# seed-raspi.net
KiCad netlist of a schematic drawn in EAGLE
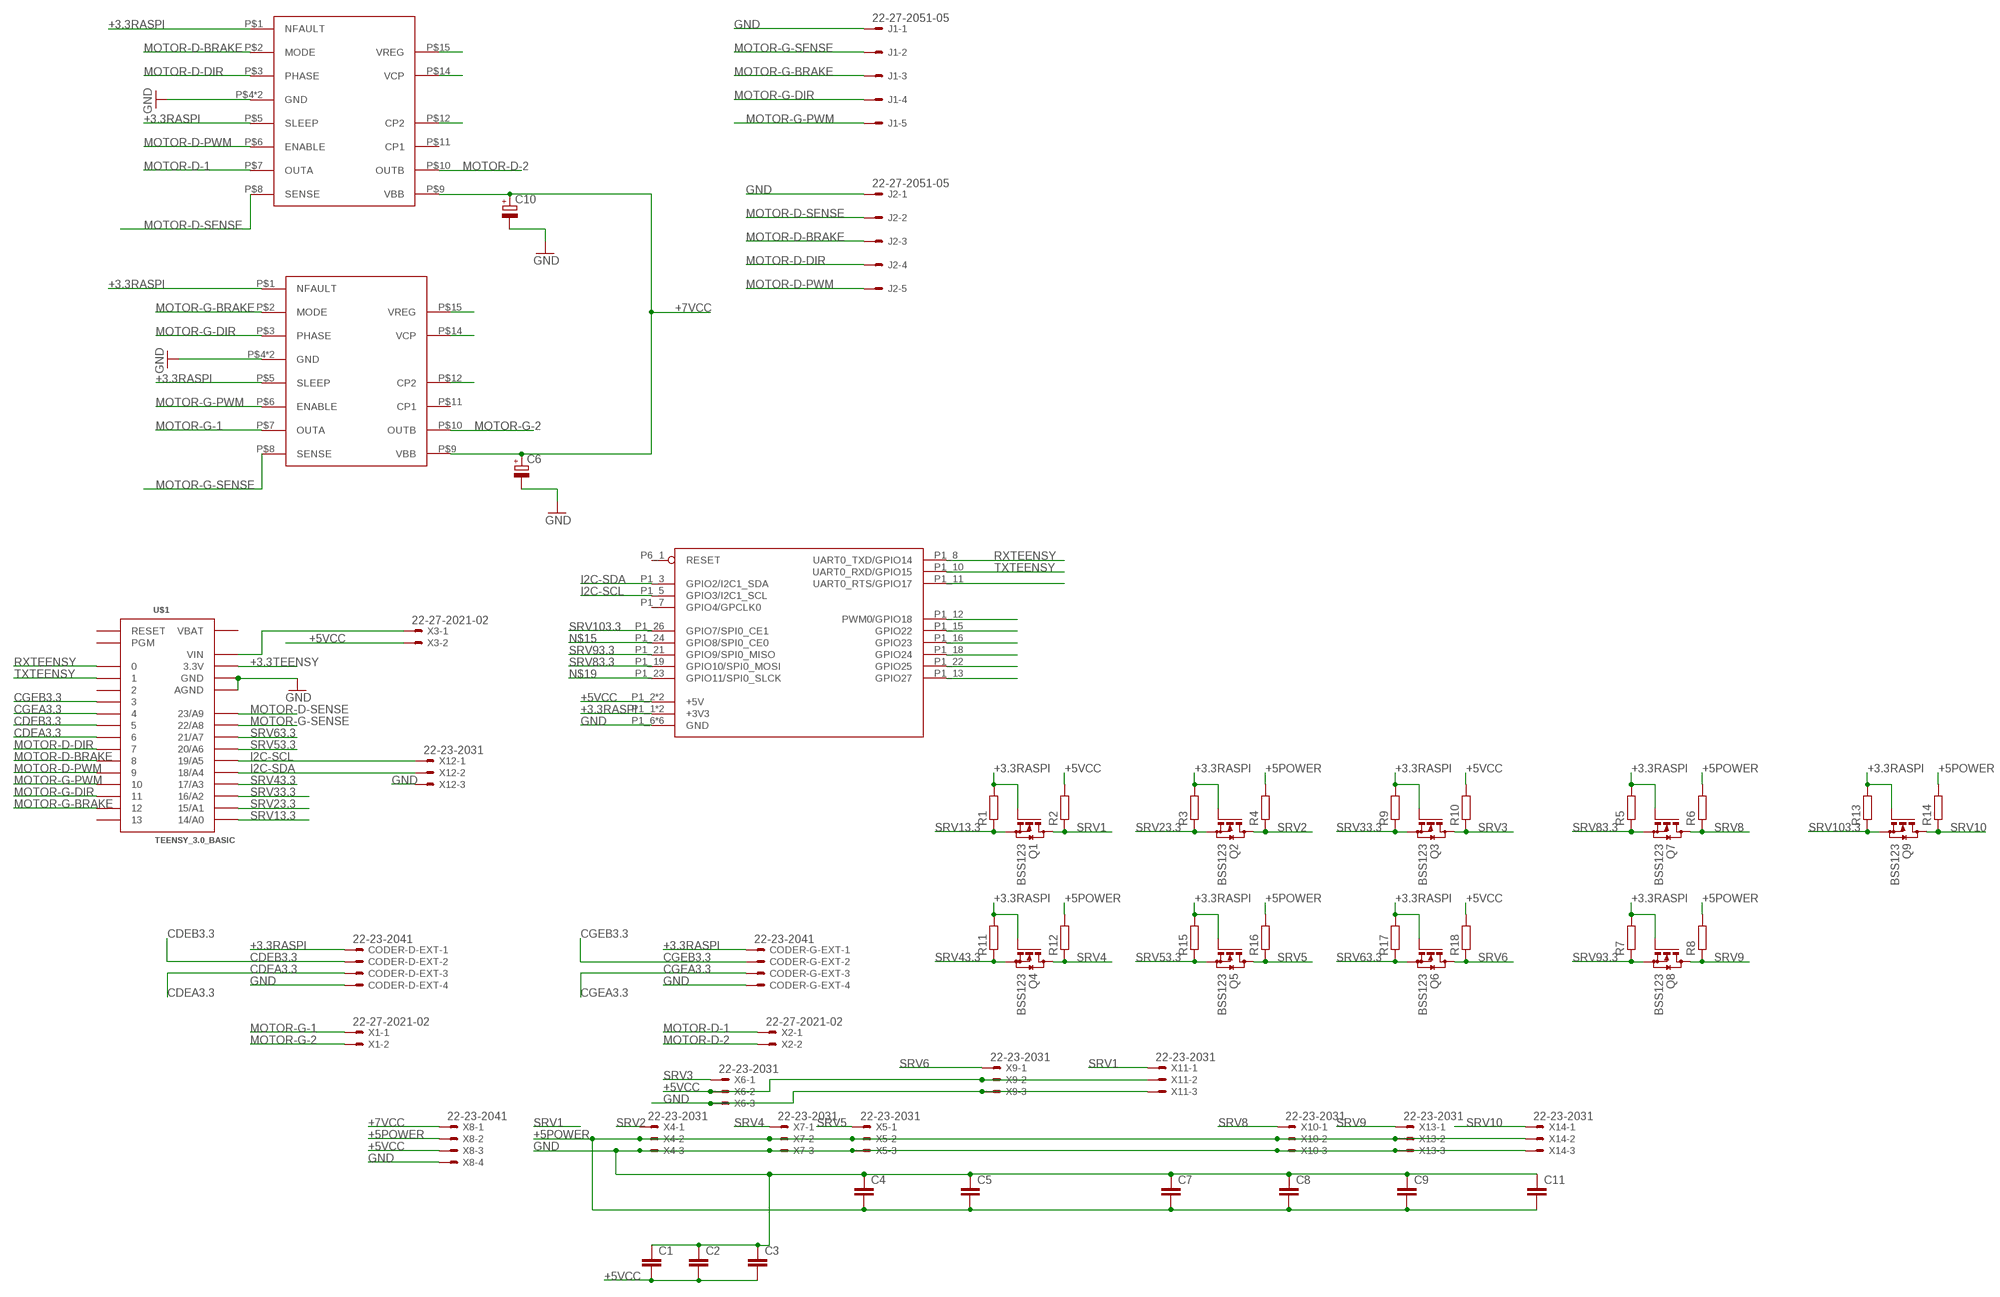
[diagram p0: schematic, sheet 2]
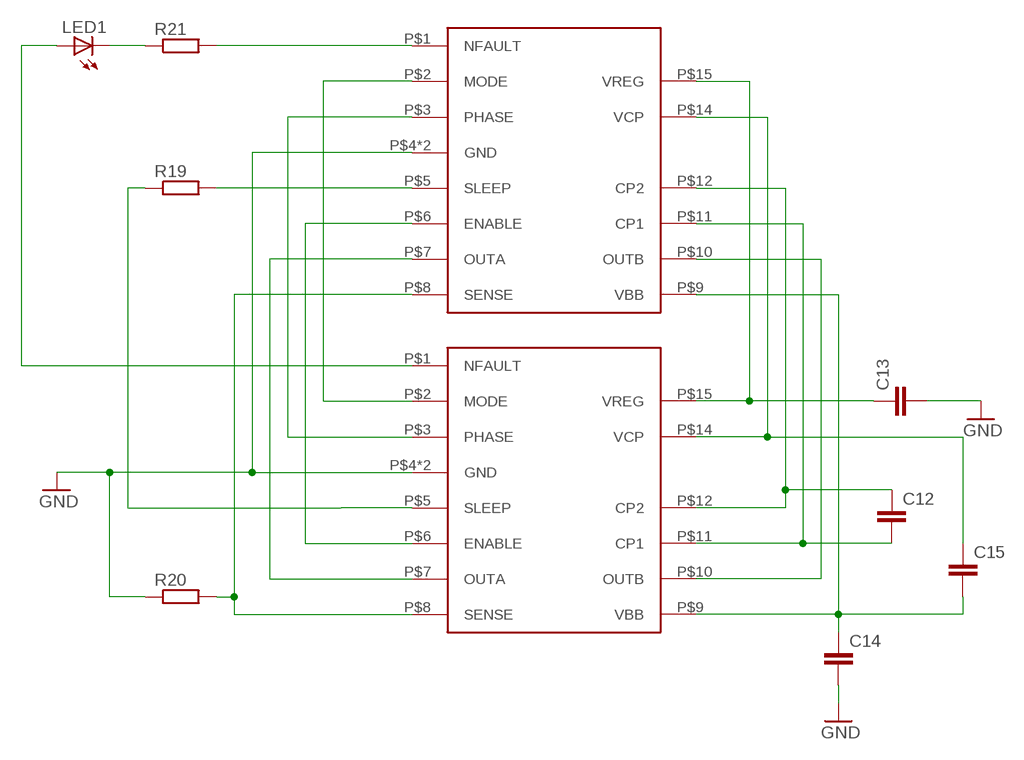
[diagram p1: schematic, sheet 3]
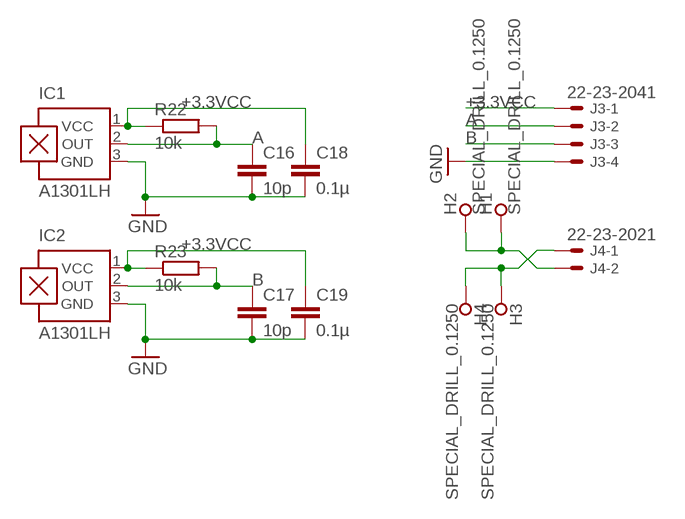
[diagram p2: schematic, sheet 4]
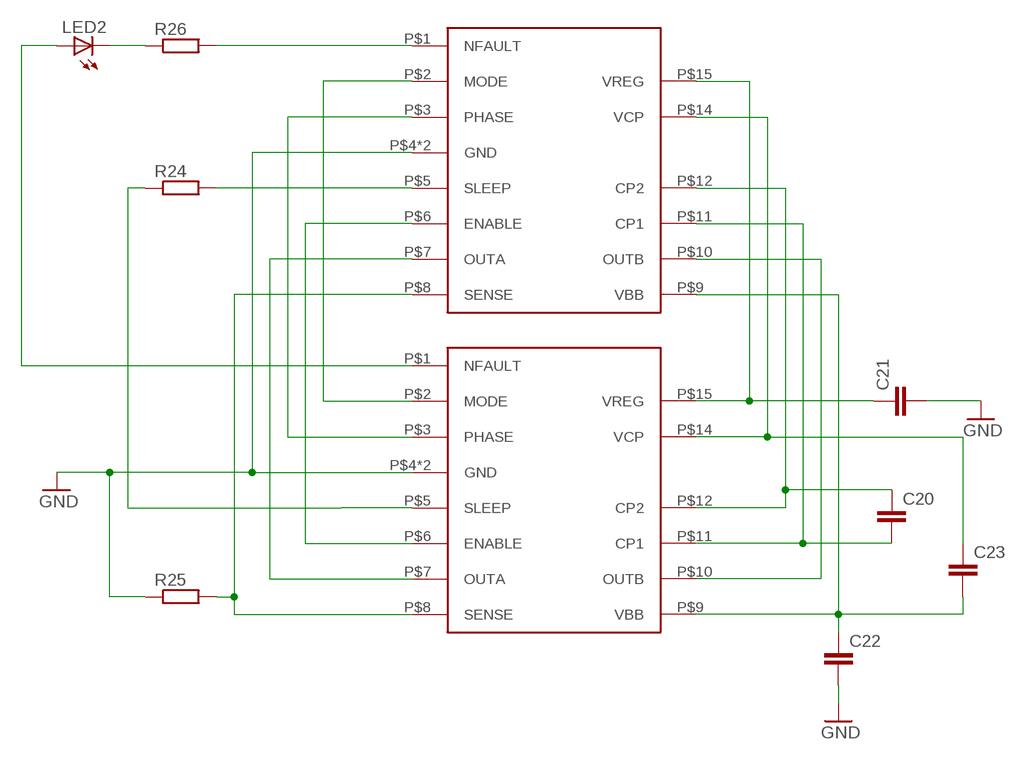
[diagram p3: schematic, sheet 5]
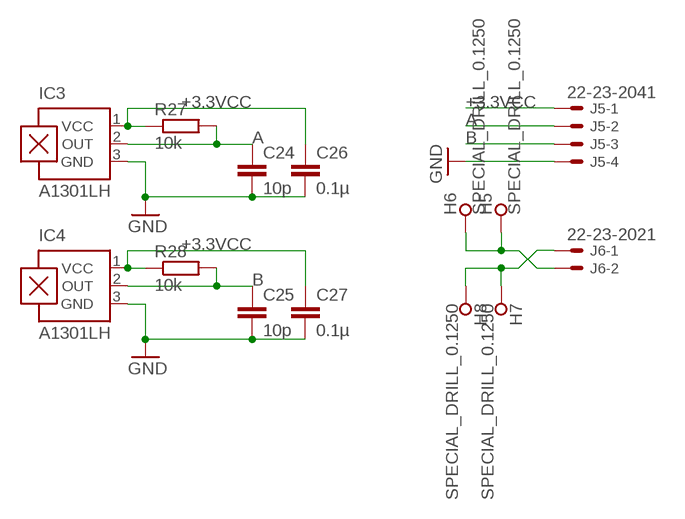
[diagram p4: schematic, sheet 6]
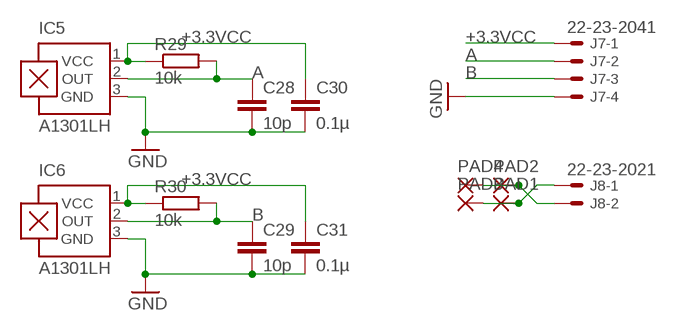
[diagram p5: schematic, sheet 7]

(export (version "E")
  (design (tool "Eeschema 10.0.6"))
  (components
    (comp (ref "C12")
      (value "C-EUC0603")
      (footprint "eagle-import:C0603")
      (libsource (lib "eagle-import") (part "C-EUC0603"))
    )
    (comp (ref "C13")
      (value "C-EUC0603")
      (footprint "eagle-import:C0603")
      (libsource (lib "eagle-import") (part "C-EUC0603"))
    )
    (comp (ref "C14")
      (value "C-EUC0603")
      (footprint "eagle-import:C0603")
      (libsource (lib "eagle-import") (part "C-EUC0603"))
    )
    (comp (ref "C15")
      (value "C-EUC0603")
      (footprint "eagle-import:C0603")
      (libsource (lib "eagle-import") (part "C-EUC0603"))
    )
    (comp (ref "LED1")
      (value "LED3MM")
      (footprint "eagle-import:LED3MM")
      (libsource (lib "eagle-import") (part "LED3MM"))
    )
    (comp (ref "R19")
      (value "R-EU_R0603")
      (footprint "eagle-import:R0603")
      (libsource (lib "eagle-import") (part "R-EU_R0603"))
    )
    (comp (ref "R20")
      (value "R-EU_R0603")
      (footprint "eagle-import:R0603")
      (libsource (lib "eagle-import") (part "R-EU_R0603"))
    )
    (comp (ref "R21")
      (value "R-EU_R0603")
      (footprint "eagle-import:R0603")
      (libsource (lib "eagle-import") (part "R-EU_R0603"))
    )
    (comp (ref "U$5")
      (value "A3950")
      (footprint "eagle-import:16TSSOP")
      (libsource (lib "eagle-import") (part "A3950"))
    )
    (comp (ref "U$6")
      (value "A3950-DIL")
      (footprint "eagle-import:DIL16")
      (libsource (lib "eagle-import") (part "A3950-DIL"))
    )
    (comp (ref "C1")
      (value "C-EUC0603K")
      (footprint "eagle-import:C0603K")
      (libsource (lib "eagle-import") (part "C-EUC0603K"))
    )
    (comp (ref "C2")
      (value "C-EUC0603K")
      (footprint "eagle-import:C0603K")
      (libsource (lib "eagle-import") (part "C-EUC0603K"))
    )
    (comp (ref "C3")
      (value "C-EUC0603K")
      (footprint "eagle-import:C0603K")
      (libsource (lib "eagle-import") (part "C-EUC0603K"))
    )
    (comp (ref "C4")
      (value "C-EUC0603K")
      (footprint "eagle-import:C0603K")
      (libsource (lib "eagle-import") (part "C-EUC0603K"))
    )
    (comp (ref "C5")
      (value "C-EUC0603K")
      (footprint "eagle-import:C0603K")
      (libsource (lib "eagle-import") (part "C-EUC0603K"))
    )
    (comp (ref "C6")
      (value "CPOL-EUE3.5-8")
      (footprint "eagle-import:E3,5-8")
      (libsource (lib "eagle-import") (part "CPOL-EUE3.5-8"))
    )
    (comp (ref "C7")
      (value "C-EUC0603K")
      (footprint "eagle-import:C0603K")
      (libsource (lib "eagle-import") (part "C-EUC0603K"))
    )
    (comp (ref "C8")
      (value "C-EUC0603K")
      (footprint "eagle-import:C0603K")
      (libsource (lib "eagle-import") (part "C-EUC0603K"))
    )
    (comp (ref "C9")
      (value "C-EUC0603K")
      (footprint "eagle-import:C0603K")
      (libsource (lib "eagle-import") (part "C-EUC0603K"))
    )
    (comp (ref "C10")
      (value "CPOL-EUE3.5-8")
      (footprint "eagle-import:E3,5-8")
      (libsource (lib "eagle-import") (part "CPOL-EUE3.5-8"))
    )
    (comp (ref "C11")
      (value "C-EUC0603K")
      (footprint "eagle-import:C0603K")
      (libsource (lib "eagle-import") (part "C-EUC0603K"))
    )
    (comp (ref "CODER-D-EXT")
      (value "22-23-2041")
      (footprint "eagle-import:22-23-2041")
      (fields (field (name "MF") "MOLEX"))
      (libsource (lib "eagle-import") (part "22-23-2041"))
    )
    (comp (ref "CODER-G-EXT")
      (value "22-23-2041")
      (footprint "eagle-import:22-23-2041")
      (fields (field (name "MF") "MOLEX"))
      (libsource (lib "eagle-import") (part "22-23-2041"))
    )
    (comp (ref "J1")
      (value "22-27-2051-05")
      (footprint "eagle-import:6410-05")
      (libsource (lib "eagle-import") (part "22-?-0527-2051"))
    )
    (comp (ref "J2")
      (value "22-27-2051-05")
      (footprint "eagle-import:6410-05")
      (libsource (lib "eagle-import") (part "22-?-0527-2051"))
    )
    (comp (ref "Q1")
      (value "BSS123")
      (footprint "eagle-import:SOT23")
      (libsource (lib "eagle-import") (part "BSS123"))
    )
    (comp (ref "Q2")
      (value "BSS123")
      (footprint "eagle-import:SOT23")
      (libsource (lib "eagle-import") (part "BSS123"))
    )
    (comp (ref "Q3")
      (value "BSS123")
      (footprint "eagle-import:SOT23")
      (libsource (lib "eagle-import") (part "BSS123"))
    )
    (comp (ref "Q4")
      (value "BSS123")
      (footprint "eagle-import:SOT23")
      (libsource (lib "eagle-import") (part "BSS123"))
    )
    (comp (ref "Q5")
      (value "BSS123")
      (footprint "eagle-import:SOT23")
      (libsource (lib "eagle-import") (part "BSS123"))
    )
    (comp (ref "Q6")
      (value "BSS123")
      (footprint "eagle-import:SOT23")
      (libsource (lib "eagle-import") (part "BSS123"))
    )
    (comp (ref "Q7")
      (value "BSS123")
      (footprint "eagle-import:SOT23")
      (libsource (lib "eagle-import") (part "BSS123"))
    )
    (comp (ref "Q8")
      (value "BSS123")
      (footprint "eagle-import:SOT23")
      (libsource (lib "eagle-import") (part "BSS123"))
    )
    (comp (ref "Q9")
      (value "BSS123")
      (footprint "eagle-import:SOT23")
      (libsource (lib "eagle-import") (part "BSS123"))
    )
    (comp (ref "R1")
      (value "R-EU_R0603")
      (footprint "eagle-import:R0603")
      (libsource (lib "eagle-import") (part "R-EU_R0603"))
    )
    (comp (ref "R2")
      (value "R-EU_R0603")
      (footprint "eagle-import:R0603")
      (libsource (lib "eagle-import") (part "R-EU_R0603"))
    )
    (comp (ref "R3")
      (value "R-EU_R0603")
      (footprint "eagle-import:R0603")
      (libsource (lib "eagle-import") (part "R-EU_R0603"))
    )
    (comp (ref "R4")
      (value "R-EU_R0603")
      (footprint "eagle-import:R0603")
      (libsource (lib "eagle-import") (part "R-EU_R0603"))
    )
    (comp (ref "R5")
      (value "R-EU_R0603")
      (footprint "eagle-import:R0603")
      (libsource (lib "eagle-import") (part "R-EU_R0603"))
    )
    (comp (ref "R6")
      (value "R-EU_R0603")
      (footprint "eagle-import:R0603")
      (libsource (lib "eagle-import") (part "R-EU_R0603"))
    )
    (comp (ref "R7")
      (value "R-EU_R0603")
      (footprint "eagle-import:R0603")
      (libsource (lib "eagle-import") (part "R-EU_R0603"))
    )
    (comp (ref "R8")
      (value "R-EU_R0603")
      (footprint "eagle-import:R0603")
      (libsource (lib "eagle-import") (part "R-EU_R0603"))
    )
    (comp (ref "R9")
      (value "R-EU_R0603")
      (footprint "eagle-import:R0603")
      (libsource (lib "eagle-import") (part "R-EU_R0603"))
    )
    (comp (ref "R10")
      (value "R-EU_R0603")
      (footprint "eagle-import:R0603")
      (libsource (lib "eagle-import") (part "R-EU_R0603"))
    )
    (comp (ref "R11")
      (value "R-EU_R0603")
      (footprint "eagle-import:R0603")
      (libsource (lib "eagle-import") (part "R-EU_R0603"))
    )
    (comp (ref "R12")
      (value "R-EU_R0603")
      (footprint "eagle-import:R0603")
      (libsource (lib "eagle-import") (part "R-EU_R0603"))
    )
    (comp (ref "R13")
      (value "R-EU_R0603")
      (footprint "eagle-import:R0603")
      (libsource (lib "eagle-import") (part "R-EU_R0603"))
    )
    (comp (ref "R14")
      (value "R-EU_R0603")
      (footprint "eagle-import:R0603")
      (libsource (lib "eagle-import") (part "R-EU_R0603"))
    )
    (comp (ref "R15")
      (value "R-EU_R0603")
      (footprint "eagle-import:R0603")
      (libsource (lib "eagle-import") (part "R-EU_R0603"))
    )
    (comp (ref "R16")
      (value "R-EU_R0603")
      (footprint "eagle-import:R0603")
      (libsource (lib "eagle-import") (part "R-EU_R0603"))
    )
    (comp (ref "R17")
      (value "R-EU_R0603")
      (footprint "eagle-import:R0603")
      (libsource (lib "eagle-import") (part "R-EU_R0603"))
    )
    (comp (ref "R18")
      (value "R-EU_R0603")
      (footprint "eagle-import:R0603")
      (libsource (lib "eagle-import") (part "R-EU_R0603"))
    )
    (comp (ref "U$1")
      (value "TEENSY_3.0_BASIC")
      (footprint "eagle-import:TEENSY_3.0_BASIC")
      (libsource (lib "eagle-import") (part "TEENSY_3.0_BASIC"))
    )
    (comp (ref "U$2")
      (value "RPI-B-V2SHIELD")
      (footprint "eagle-import:RPI-B-V2-SHIELD")
      (libsource (lib "eagle-import") (part "RPI-B-V2SHIELD"))
    )
    (comp (ref "U$3")
      (value "A3950-DIL")
      (footprint "eagle-import:DIL16")
      (libsource (lib "eagle-import") (part "A3950-DIL"))
    )
    (comp (ref "U$4")
      (value "A3950-DIL")
      (footprint "eagle-import:DIL16")
      (libsource (lib "eagle-import") (part "A3950-DIL"))
    )
    (comp (ref "X1")
      (value "22-27-2021-02")
      (footprint "eagle-import:6410-02")
      (libsource (lib "eagle-import") (part "22-?-0227-2021"))
    )
    (comp (ref "X2")
      (value "22-27-2021-02")
      (footprint "eagle-import:6410-02")
      (libsource (lib "eagle-import") (part "22-?-0227-2021"))
    )
    (comp (ref "X3")
      (value "22-27-2021-02")
      (footprint "eagle-import:6410-02")
      (libsource (lib "eagle-import") (part "22-?-0227-2021"))
    )
    (comp (ref "X4")
      (value "22-23-2031")
      (footprint "eagle-import:22-23-2031")
      (fields (field (name "MF") "MOLEX"))
      (libsource (lib "eagle-import") (part "22-23-2031"))
    )
    (comp (ref "X5")
      (value "22-23-2031")
      (footprint "eagle-import:22-23-2031")
      (fields (field (name "MF") "MOLEX"))
      (libsource (lib "eagle-import") (part "22-23-2031"))
    )
    (comp (ref "X6")
      (value "22-23-2031")
      (footprint "eagle-import:22-23-2031")
      (fields (field (name "MF") "MOLEX"))
      (libsource (lib "eagle-import") (part "22-23-2031"))
    )
    (comp (ref "X7")
      (value "22-23-2031")
      (footprint "eagle-import:22-23-2031")
      (fields (field (name "MF") "MOLEX"))
      (libsource (lib "eagle-import") (part "22-23-2031"))
    )
    (comp (ref "X8")
      (value "22-23-2041")
      (footprint "eagle-import:22-23-2041")
      (fields (field (name "MF") "MOLEX"))
      (libsource (lib "eagle-import") (part "22-23-2041"))
    )
    (comp (ref "X9")
      (value "22-23-2031")
      (footprint "eagle-import:22-23-2031")
      (fields (field (name "MF") "MOLEX"))
      (libsource (lib "eagle-import") (part "22-23-2031"))
    )
    (comp (ref "X10")
      (value "22-23-2031")
      (footprint "eagle-import:22-23-2031")
      (fields (field (name "MF") "MOLEX"))
      (libsource (lib "eagle-import") (part "22-23-2031"))
    )
    (comp (ref "X11")
      (value "22-23-2031")
      (footprint "eagle-import:22-23-2031")
      (fields (field (name "MF") "MOLEX"))
      (libsource (lib "eagle-import") (part "22-23-2031"))
    )
    (comp (ref "X12")
      (value "22-23-2031")
      (footprint "eagle-import:22-23-2031")
      (fields (field (name "MF") "MOLEX"))
      (libsource (lib "eagle-import") (part "22-23-2031"))
    )
    (comp (ref "X13")
      (value "22-23-2031")
      (footprint "eagle-import:22-23-2031")
      (fields (field (name "MF") "MOLEX"))
      (libsource (lib "eagle-import") (part "22-23-2031"))
    )
    (comp (ref "X14")
      (value "22-23-2031")
      (footprint "eagle-import:22-23-2031")
      (fields (field (name "MF") "MOLEX"))
      (libsource (lib "eagle-import") (part "22-23-2031"))
    )
    (comp (ref "C24")
      (value "10p")
      (footprint "eagle-import:C0805")
      (libsource (lib "eagle-import") (part "C-EUC0805"))
    )
    (comp (ref "C25")
      (value "10p")
      (footprint "eagle-import:C0805")
      (libsource (lib "eagle-import") (part "C-EUC0805"))
    )
    (comp (ref "C26")
      (value "0.1µ")
      (footprint "eagle-import:C0805")
      (libsource (lib "eagle-import") (part "C-EUC0805"))
    )
    (comp (ref "C27")
      (value "0.1µ")
      (footprint "eagle-import:C0805")
      (libsource (lib "eagle-import") (part "C-EUC0805"))
    )
    (comp (ref "H5")
      (value "SPECIAL_DRILL_0.1250")
      (footprint "eagle-import:PAD_0.1250")
      (libsource (lib "eagle-import") (part "SPECIAL_DRILL_0.1250"))
    )
    (comp (ref "H6")
      (value "SPECIAL_DRILL_0.1250")
      (footprint "eagle-import:PAD_0.1250")
      (libsource (lib "eagle-import") (part "SPECIAL_DRILL_0.1250"))
    )
    (comp (ref "H7")
      (value "SPECIAL_DRILL_0.1250")
      (footprint "eagle-import:PAD_0.1250")
      (libsource (lib "eagle-import") (part "SPECIAL_DRILL_0.1250"))
    )
    (comp (ref "H8")
      (value "SPECIAL_DRILL_0.1250")
      (footprint "eagle-import:PAD_0.1250")
      (libsource (lib "eagle-import") (part "SPECIAL_DRILL_0.1250"))
    )
    (comp (ref "IC3")
      (value "A1301LH")
      (footprint "eagle-import:SOT23-W")
      (fields (field (name "MF") "ALLEGRO MICROSYSTEMS, INC.") (field (name "MPN") "A1301ELHLT-T"))
      (libsource (lib "eagle-import") (part "A13?LH01"))
    )
    (comp (ref "IC4")
      (value "A1301LH")
      (footprint "eagle-import:SOT23-W")
      (fields (field (name "MF") "ALLEGRO MICROSYSTEMS, INC.") (field (name "MPN") "A1301ELHLT-T"))
      (libsource (lib "eagle-import") (part "A13?LH01"))
    )
    (comp (ref "J5")
      (value "22-23-2041")
      (footprint "eagle-import:22-23-2041")
      (fields (field (name "MF") "MOLEX"))
      (libsource (lib "eagle-import") (part "22-23-2041"))
    )
    (comp (ref "J6")
      (value "22-23-2021")
      (footprint "eagle-import:22-23-2021")
      (fields (field (name "MF") "MOLEX"))
      (libsource (lib "eagle-import") (part "22-23-2021"))
    )
    (comp (ref "R27")
      (value "10k")
      (footprint "eagle-import:R0805")
      (libsource (lib "eagle-import") (part "R-EU_R0805"))
    )
    (comp (ref "R28")
      (value "10k")
      (footprint "eagle-import:R0805")
      (libsource (lib "eagle-import") (part "R-EU_R0805"))
    )
    (comp (ref "C16")
      (value "10p")
      (footprint "eagle-import:C0805")
      (libsource (lib "eagle-import") (part "C-EUC0805"))
    )
    (comp (ref "C17")
      (value "10p")
      (footprint "eagle-import:C0805")
      (libsource (lib "eagle-import") (part "C-EUC0805"))
    )
    (comp (ref "C18")
      (value "0.1µ")
      (footprint "eagle-import:C0805")
      (libsource (lib "eagle-import") (part "C-EUC0805"))
    )
    (comp (ref "C19")
      (value "0.1µ")
      (footprint "eagle-import:C0805")
      (libsource (lib "eagle-import") (part "C-EUC0805"))
    )
    (comp (ref "H1")
      (value "SPECIAL_DRILL_0.1250")
      (footprint "eagle-import:PAD_0.1250")
      (libsource (lib "eagle-import") (part "SPECIAL_DRILL_0.1250"))
    )
    (comp (ref "H2")
      (value "SPECIAL_DRILL_0.1250")
      (footprint "eagle-import:PAD_0.1250")
      (libsource (lib "eagle-import") (part "SPECIAL_DRILL_0.1250"))
    )
    (comp (ref "H3")
      (value "SPECIAL_DRILL_0.1250")
      (footprint "eagle-import:PAD_0.1250")
      (libsource (lib "eagle-import") (part "SPECIAL_DRILL_0.1250"))
    )
    (comp (ref "H4")
      (value "SPECIAL_DRILL_0.1250")
      (footprint "eagle-import:PAD_0.1250")
      (libsource (lib "eagle-import") (part "SPECIAL_DRILL_0.1250"))
    )
    (comp (ref "IC1")
      (value "A1301LH")
      (footprint "eagle-import:SOT23-W")
      (fields (field (name "MF") "ALLEGRO MICROSYSTEMS, INC.") (field (name "MPN") "A1301ELHLT-T"))
      (libsource (lib "eagle-import") (part "A13?LH01"))
    )
    (comp (ref "IC2")
      (value "A1301LH")
      (footprint "eagle-import:SOT23-W")
      (fields (field (name "MF") "ALLEGRO MICROSYSTEMS, INC.") (field (name "MPN") "A1301ELHLT-T"))
      (libsource (lib "eagle-import") (part "A13?LH01"))
    )
    (comp (ref "J3")
      (value "22-23-2041")
      (footprint "eagle-import:22-23-2041")
      (fields (field (name "MF") "MOLEX"))
      (libsource (lib "eagle-import") (part "22-23-2041"))
    )
    (comp (ref "J4")
      (value "22-23-2021")
      (footprint "eagle-import:22-23-2021")
      (fields (field (name "MF") "MOLEX"))
      (libsource (lib "eagle-import") (part "22-23-2021"))
    )
    (comp (ref "R22")
      (value "10k")
      (footprint "eagle-import:R0805")
      (libsource (lib "eagle-import") (part "R-EU_R0805"))
    )
    (comp (ref "R23")
      (value "10k")
      (footprint "eagle-import:R0805")
      (libsource (lib "eagle-import") (part "R-EU_R0805"))
    )
    (comp (ref "C20")
      (value "C-EUC0603")
      (footprint "eagle-import:C0603")
      (libsource (lib "eagle-import") (part "C-EUC0603"))
    )
    (comp (ref "C21")
      (value "C-EUC0603")
      (footprint "eagle-import:C0603")
      (libsource (lib "eagle-import") (part "C-EUC0603"))
    )
    (comp (ref "C22")
      (value "C-EUC0603")
      (footprint "eagle-import:C0603")
      (libsource (lib "eagle-import") (part "C-EUC0603"))
    )
    (comp (ref "C23")
      (value "C-EUC0603")
      (footprint "eagle-import:C0603")
      (libsource (lib "eagle-import") (part "C-EUC0603"))
    )
    (comp (ref "LED2")
      (value "LED3MM")
      (footprint "eagle-import:LED3MM")
      (libsource (lib "eagle-import") (part "LED3MM"))
    )
    (comp (ref "R24")
      (value "R-EU_R0603")
      (footprint "eagle-import:R0603")
      (libsource (lib "eagle-import") (part "R-EU_R0603"))
    )
    (comp (ref "R25")
      (value "R-EU_R0603")
      (footprint "eagle-import:R0603")
      (libsource (lib "eagle-import") (part "R-EU_R0603"))
    )
    (comp (ref "R26")
      (value "R-EU_R0603")
      (footprint "eagle-import:R0603")
      (libsource (lib "eagle-import") (part "R-EU_R0603"))
    )
    (comp (ref "U$7")
      (value "A3950")
      (footprint "eagle-import:16TSSOP")
      (libsource (lib "eagle-import") (part "A3950"))
    )
    (comp (ref "U$8")
      (value "A3950-DIL")
      (footprint "eagle-import:DIL16")
      (libsource (lib "eagle-import") (part "A3950-DIL"))
    )
    (comp (ref "C28")
      (value "10p")
      (footprint "eagle-import:C0805")
      (libsource (lib "eagle-import") (part "C-EUC0805"))
    )
    (comp (ref "C29")
      (value "10p")
      (footprint "eagle-import:C0805")
      (libsource (lib "eagle-import") (part "C-EUC0805"))
    )
    (comp (ref "C30")
      (value "0.1µ")
      (footprint "eagle-import:C0805")
      (libsource (lib "eagle-import") (part "C-EUC0805"))
    )
    (comp (ref "C31")
      (value "0.1µ")
      (footprint "eagle-import:C0805")
      (libsource (lib "eagle-import") (part "C-EUC0805"))
    )
    (comp (ref "IC5")
      (value "A1301LH")
      (footprint "eagle-import:SOT23-W")
      (fields (field (name "MF") "ALLEGRO MICROSYSTEMS, INC.") (field (name "MPN") "A1301ELHLT-T"))
      (libsource (lib "eagle-import") (part "A13?LH01"))
    )
    (comp (ref "IC6")
      (value "A1301LH")
      (footprint "eagle-import:SOT23-W")
      (fields (field (name "MF") "ALLEGRO MICROSYSTEMS, INC.") (field (name "MPN") "A1301ELHLT-T"))
      (libsource (lib "eagle-import") (part "A13?LH01"))
    )
    (comp (ref "J7")
      (value "22-23-2041")
      (footprint "eagle-import:22-23-2041")
      (fields (field (name "MF") "MOLEX"))
      (libsource (lib "eagle-import") (part "22-23-2041"))
    )
    (comp (ref "J8")
      (value "22-23-2021")
      (footprint "eagle-import:22-23-2021")
      (fields (field (name "MF") "MOLEX"))
      (libsource (lib "eagle-import") (part "22-23-2021"))
    )
    (comp (ref "PAD1")
      (value "3,81/1,4")
      (footprint "eagle-import:3,81_1,4")
      (libsource (lib "eagle-import") (part "3,81/1,4"))
    )
    (comp (ref "PAD2")
      (value "3,81/1,4")
      (footprint "eagle-import:3,81_1,4")
      (libsource (lib "eagle-import") (part "3,81/1,4"))
    )
    (comp (ref "PAD3")
      (value "3,81/1,4")
      (footprint "eagle-import:3,81_1,4")
      (libsource (lib "eagle-import") (part "3,81/1,4"))
    )
    (comp (ref "PAD4")
      (value "3,81/1,4")
      (footprint "eagle-import:3,81_1,4")
      (libsource (lib "eagle-import") (part "3,81/1,4"))
    )
    (comp (ref "R29")
      (value "10k")
      (footprint "eagle-import:R0805")
      (libsource (lib "eagle-import") (part "R-EU_R0805"))
    )
    (comp (ref "R30")
      (value "10k")
      (footprint "eagle-import:R0805")
      (libsource (lib "eagle-import") (part "R-EU_R0805"))
    )
  )
  (nets
    (net (code "1") (name "+3.3RASPI") (class "Default")
      (node (ref "CODER-D-EXT") (pin "1") (pinfunction "S_1") (pintype "passive"))
      (node (ref "CODER-G-EXT") (pin "1") (pinfunction "S_1") (pintype "passive"))
      (node (ref "Q1") (pin "1") (pinfunction "G_1") (pintype "passive"))
      (node (ref "Q2") (pin "1") (pinfunction "G_1") (pintype "passive"))
      (node (ref "Q3") (pin "1") (pinfunction "G_1") (pintype "passive"))
      (node (ref "Q4") (pin "1") (pinfunction "G_1") (pintype "passive"))
      (node (ref "Q5") (pin "1") (pinfunction "G_1") (pintype "passive"))
      (node (ref "Q6") (pin "1") (pinfunction "G_1") (pintype "passive"))
      (node (ref "Q7") (pin "1") (pinfunction "G_1") (pintype "passive"))
      (node (ref "Q8") (pin "1") (pinfunction "G_1") (pintype "passive"))
      (node (ref "Q9") (pin "1") (pinfunction "G_1") (pintype "passive"))
      (node (ref "R1") (pin "2") (pinfunction "2_2") (pintype "passive"))
      (node (ref "R11") (pin "2") (pinfunction "2_2") (pintype "passive"))
      (node (ref "R13") (pin "2") (pinfunction "2_2") (pintype "passive"))
      (node (ref "R15") (pin "2") (pinfunction "2_2") (pintype "passive"))
      (node (ref "R17") (pin "2") (pinfunction "2_2") (pintype "passive"))
      (node (ref "R3") (pin "2") (pinfunction "2_2") (pintype "passive"))
      (node (ref "R5") (pin "2") (pinfunction "2_2") (pintype "passive"))
      (node (ref "R7") (pin "2") (pinfunction "2_2") (pintype "passive"))
      (node (ref "R9") (pin "2") (pinfunction "2_2") (pintype "passive"))
      (node (ref "U$2") (pin "P1_1") (pinfunction "+3V3_P1_1") (pintype "power_in"))
      (node (ref "U$2") (pin "P1_17") (pinfunction "+3V3_P1_17") (pintype "power_in"))
      (node (ref "U$3") (pin "P$1") (pinfunction "NFAULT_P$1") (pintype "bidirectional"))
      (node (ref "U$3") (pin "P$5") (pinfunction "SLEEP_P$5") (pintype "bidirectional"))
      (node (ref "U$4") (pin "P$1") (pinfunction "NFAULT_P$1") (pintype "bidirectional"))
      (node (ref "U$4") (pin "P$5") (pinfunction "SLEEP_P$5") (pintype "bidirectional"))
    )
    (net (code "2") (name "+3.3TEENSY") (class "Default")
      (node (ref "U$1") (pin "3.3V") (pinfunction "3.3V_3.3V") (pintype "power_in"))
      (node (ref "U$1") (pin "3.3V1") (pinfunction "3.3V_3.3V1") (pintype "power_in"))
    )
    (net (code "3") (name "+3.3VCC") (class "Default")
      (node (ref "C18") (pin "1") (pinfunction "1_1") (pintype "passive"))
      (node (ref "C19") (pin "1") (pinfunction "1_1") (pintype "passive"))
      (node (ref "C26") (pin "1") (pinfunction "1_1") (pintype "passive"))
      (node (ref "C27") (pin "1") (pinfunction "1_1") (pintype "passive"))
      (node (ref "C30") (pin "1") (pinfunction "1_1") (pintype "passive"))
      (node (ref "C31") (pin "1") (pinfunction "1_1") (pintype "passive"))
      (node (ref "IC1") (pin "1") (pinfunction "VCC_1") (pintype "power_in"))
      (node (ref "IC2") (pin "1") (pinfunction "VCC_1") (pintype "power_in"))
      (node (ref "IC3") (pin "1") (pinfunction "VCC_1") (pintype "power_in"))
      (node (ref "IC4") (pin "1") (pinfunction "VCC_1") (pintype "power_in"))
      (node (ref "IC5") (pin "1") (pinfunction "VCC_1") (pintype "power_in"))
      (node (ref "IC6") (pin "1") (pinfunction "VCC_1") (pintype "power_in"))
      (node (ref "J3") (pin "1") (pinfunction "S_1") (pintype "passive"))
      (node (ref "J5") (pin "1") (pinfunction "S_1") (pintype "passive"))
      (node (ref "J7") (pin "1") (pinfunction "S_1") (pintype "passive"))
      (node (ref "R22") (pin "1") (pinfunction "1_1") (pintype "passive"))
      (node (ref "R23") (pin "1") (pinfunction "1_1") (pintype "passive"))
      (node (ref "R27") (pin "1") (pinfunction "1_1") (pintype "passive"))
      (node (ref "R28") (pin "1") (pinfunction "1_1") (pintype "passive"))
      (node (ref "R29") (pin "1") (pinfunction "1_1") (pintype "passive"))
      (node (ref "R30") (pin "1") (pinfunction "1_1") (pintype "passive"))
    )
    (net (code "4") (name "+5POWER") (class "Default")
      (node (ref "C11") (pin "2") (pinfunction "2_2") (pintype "passive"))
      (node (ref "C4") (pin "2") (pinfunction "2_2") (pintype "passive"))
      (node (ref "C5") (pin "2") (pinfunction "2_2") (pintype "passive"))
      (node (ref "C7") (pin "2") (pinfunction "2_2") (pintype "passive"))
      (node (ref "C8") (pin "2") (pinfunction "2_2") (pintype "passive"))
      (node (ref "C9") (pin "2") (pinfunction "2_2") (pintype "passive"))
      (node (ref "R12") (pin "2") (pinfunction "2_2") (pintype "passive"))
      (node (ref "R14") (pin "2") (pinfunction "2_2") (pintype "passive"))
      (node (ref "R16") (pin "2") (pinfunction "2_2") (pintype "passive"))
      (node (ref "R4") (pin "2") (pinfunction "2_2") (pintype "passive"))
      (node (ref "R6") (pin "2") (pinfunction "2_2") (pintype "passive"))
      (node (ref "R8") (pin "2") (pinfunction "2_2") (pintype "passive"))
      (node (ref "X10") (pin "2") (pinfunction "S_2") (pintype "passive"))
      (node (ref "X13") (pin "2") (pinfunction "S_2") (pintype "passive"))
      (node (ref "X14") (pin "2") (pinfunction "S_2") (pintype "passive"))
      (node (ref "X4") (pin "2") (pinfunction "S_2") (pintype "passive"))
      (node (ref "X5") (pin "2") (pinfunction "S_2") (pintype "passive"))
      (node (ref "X7") (pin "2") (pinfunction "S_2") (pintype "passive"))
      (node (ref "X8") (pin "2") (pinfunction "S_2") (pintype "passive"))
    )
    (net (code "5") (name "+5VCC") (class "Default")
      (node (ref "C1") (pin "2") (pinfunction "2_2") (pintype "passive"))
      (node (ref "C2") (pin "2") (pinfunction "2_2") (pintype "passive"))
      (node (ref "C3") (pin "2") (pinfunction "2_2") (pintype "passive"))
      (node (ref "R10") (pin "2") (pinfunction "2_2") (pintype "passive"))
      (node (ref "R18") (pin "2") (pinfunction "2_2") (pintype "passive"))
      (node (ref "R2") (pin "2") (pinfunction "2_2") (pintype "passive"))
      (node (ref "U$2") (pin "P1_2") (pinfunction "+5V_P1_2") (pintype "power_in"))
      (node (ref "U$2") (pin "P1_4") (pinfunction "+5V_P1_4") (pintype "power_in"))
      (node (ref "X11") (pin "2") (pinfunction "S_2") (pintype "passive"))
      (node (ref "X3") (pin "2") (pinfunction "S_2") (pintype "passive"))
      (node (ref "X6") (pin "2") (pinfunction "S_2") (pintype "passive"))
      (node (ref "X8") (pin "3") (pinfunction "S_3") (pintype "passive"))
      (node (ref "X9") (pin "2") (pinfunction "S_2") (pintype "passive"))
    )
    (net (code "6") (name "+7VCC") (class "Default")
      (node (ref "C10") (pin "+") (pinfunction "+_+") (pintype "passive"))
      (node (ref "C6") (pin "+") (pinfunction "+_+") (pintype "passive"))
      (node (ref "U$3") (pin "P$9") (pinfunction "VBB_P$9") (pintype "bidirectional"))
      (node (ref "U$4") (pin "P$9") (pinfunction "VBB_P$9") (pintype "bidirectional"))
      (node (ref "X8") (pin "1") (pinfunction "S_1") (pintype "passive"))
    )
    (net (code "7") (name "A") (class "Default")
      (node (ref "C16") (pin "1") (pinfunction "1_1") (pintype "passive"))
      (node (ref "C24") (pin "1") (pinfunction "1_1") (pintype "passive"))
      (node (ref "C28") (pin "1") (pinfunction "1_1") (pintype "passive"))
      (node (ref "IC1") (pin "2") (pinfunction "OUT_2") (pintype "output"))
      (node (ref "IC3") (pin "2") (pinfunction "OUT_2") (pintype "output"))
      (node (ref "IC5") (pin "2") (pinfunction "OUT_2") (pintype "output"))
      (node (ref "J3") (pin "2") (pinfunction "S_2") (pintype "passive"))
      (node (ref "J5") (pin "2") (pinfunction "S_2") (pintype "passive"))
      (node (ref "J7") (pin "2") (pinfunction "S_2") (pintype "passive"))
      (node (ref "R22") (pin "2") (pinfunction "2_2") (pintype "passive"))
      (node (ref "R27") (pin "2") (pinfunction "2_2") (pintype "passive"))
      (node (ref "R29") (pin "2") (pinfunction "2_2") (pintype "passive"))
    )
    (net (code "8") (name "B") (class "Default")
      (node (ref "C17") (pin "1") (pinfunction "1_1") (pintype "passive"))
      (node (ref "C25") (pin "1") (pinfunction "1_1") (pintype "passive"))
      (node (ref "C29") (pin "1") (pinfunction "1_1") (pintype "passive"))
      (node (ref "IC2") (pin "2") (pinfunction "OUT_2") (pintype "output"))
      (node (ref "IC4") (pin "2") (pinfunction "OUT_2") (pintype "output"))
      (node (ref "IC6") (pin "2") (pinfunction "OUT_2") (pintype "output"))
      (node (ref "J3") (pin "3") (pinfunction "S_3") (pintype "passive"))
      (node (ref "J5") (pin "3") (pinfunction "S_3") (pintype "passive"))
      (node (ref "J7") (pin "3") (pinfunction "S_3") (pintype "passive"))
      (node (ref "R23") (pin "2") (pinfunction "2_2") (pintype "passive"))
      (node (ref "R28") (pin "2") (pinfunction "2_2") (pintype "passive"))
      (node (ref "R30") (pin "2") (pinfunction "2_2") (pintype "passive"))
    )
    (net (code "9") (name "CDEA3.3") (class "Default")
      (node (ref "CODER-D-EXT") (pin "3") (pinfunction "S_3") (pintype "passive"))
      (node (ref "U$1") (pin "6") (pinfunction "6_6") (pintype "bidirectional"))
    )
    (net (code "10") (name "CDEB3.3") (class "Default")
      (node (ref "CODER-D-EXT") (pin "2") (pinfunction "S_2") (pintype "passive"))
      (node (ref "U$1") (pin "5") (pinfunction "5_5") (pintype "bidirectional"))
    )
    (net (code "11") (name "CGEA3.3") (class "Default")
      (node (ref "CODER-G-EXT") (pin "3") (pinfunction "S_3") (pintype "passive"))
      (node (ref "U$1") (pin "4") (pinfunction "4_4") (pintype "bidirectional"))
    )
    (net (code "12") (name "CGEB3.3") (class "Default")
      (node (ref "CODER-G-EXT") (pin "2") (pinfunction "S_2") (pintype "passive"))
      (node (ref "U$1") (pin "3") (pinfunction "3_3") (pintype "bidirectional"))
    )
    (net (code "13") (name "GND") (class "Default")
      (node (ref "C1") (pin "1") (pinfunction "1_1") (pintype "passive"))
      (node (ref "C10") (pin "-") (pinfunction "-_-") (pintype "passive"))
      (node (ref "C11") (pin "1") (pinfunction "1_1") (pintype "passive"))
      (node (ref "C13") (pin "2") (pinfunction "2_2") (pintype "passive"))
      (node (ref "C14") (pin "2") (pinfunction "2_2") (pintype "passive"))
      (node (ref "C16") (pin "2") (pinfunction "2_2") (pintype "passive"))
      (node (ref "C17") (pin "2") (pinfunction "2_2") (pintype "passive"))
      (node (ref "C18") (pin "2") (pinfunction "2_2") (pintype "passive"))
      (node (ref "C19") (pin "2") (pinfunction "2_2") (pintype "passive"))
      (node (ref "C2") (pin "1") (pinfunction "1_1") (pintype "passive"))
      (node (ref "C21") (pin "2") (pinfunction "2_2") (pintype "passive"))
      (node (ref "C22") (pin "2") (pinfunction "2_2") (pintype "passive"))
      (node (ref "C24") (pin "2") (pinfunction "2_2") (pintype "passive"))
      (node (ref "C25") (pin "2") (pinfunction "2_2") (pintype "passive"))
      (node (ref "C26") (pin "2") (pinfunction "2_2") (pintype "passive"))
      (node (ref "C27") (pin "2") (pinfunction "2_2") (pintype "passive"))
      (node (ref "C28") (pin "2") (pinfunction "2_2") (pintype "passive"))
      (node (ref "C29") (pin "2") (pinfunction "2_2") (pintype "passive"))
      (node (ref "C3") (pin "1") (pinfunction "1_1") (pintype "passive"))
      (node (ref "C30") (pin "2") (pinfunction "2_2") (pintype "passive"))
      (node (ref "C31") (pin "2") (pinfunction "2_2") (pintype "passive"))
      (node (ref "C4") (pin "1") (pinfunction "1_1") (pintype "passive"))
      (node (ref "C5") (pin "1") (pinfunction "1_1") (pintype "passive"))
      (node (ref "C6") (pin "-") (pinfunction "-_-") (pintype "passive"))
      (node (ref "C7") (pin "1") (pinfunction "1_1") (pintype "passive"))
      (node (ref "C8") (pin "1") (pinfunction "1_1") (pintype "passive"))
      (node (ref "C9") (pin "1") (pinfunction "1_1") (pintype "passive"))
      (node (ref "CODER-D-EXT") (pin "4") (pinfunction "S_4") (pintype "passive"))
      (node (ref "CODER-G-EXT") (pin "4") (pinfunction "S_4") (pintype "passive"))
      (node (ref "IC1") (pin "3") (pinfunction "GND_3") (pintype "power_in"))
      (node (ref "IC2") (pin "3") (pinfunction "GND_3") (pintype "power_in"))
      (node (ref "IC3") (pin "3") (pinfunction "GND_3") (pintype "power_in"))
      (node (ref "IC4") (pin "3") (pinfunction "GND_3") (pintype "power_in"))
      (node (ref "IC5") (pin "3") (pinfunction "GND_3") (pintype "power_in"))
      (node (ref "IC6") (pin "3") (pinfunction "GND_3") (pintype "power_in"))
      (node (ref "J1") (pin "1") (pinfunction "S_1") (pintype "passive"))
      (node (ref "J2") (pin "1") (pinfunction "S_1") (pintype "passive"))
      (node (ref "J3") (pin "4") (pinfunction "S_4") (pintype "passive"))
      (node (ref "J5") (pin "4") (pinfunction "S_4") (pintype "passive"))
      (node (ref "J7") (pin "4") (pinfunction "S_4") (pintype "passive"))
      (node (ref "R20") (pin "1") (pinfunction "1_1") (pintype "passive"))
      (node (ref "R25") (pin "1") (pinfunction "1_1") (pintype "passive"))
      (node (ref "U$1") (pin "AGND") (pinfunction "AGND_AGND") (pintype "power_in"))
      (node (ref "U$1") (pin "GND") (pinfunction "GND_GND") (pintype "power_in"))
      (node (ref "U$1") (pin "GND1") (pinfunction "GND_GND1") (pintype "power_in"))
      (node (ref "U$2") (pin "P1_14") (pinfunction "GND_P1_14") (pintype "power_in"))
      (node (ref "U$2") (pin "P1_20") (pinfunction "GND_P1_20") (pintype "power_in"))
      (node (ref "U$2") (pin "P1_25") (pinfunction "GND_P1_25") (pintype "power_in"))
      (node (ref "U$2") (pin "P1_6") (pinfunction "GND_P1_6") (pintype "power_in"))
      (node (ref "U$2") (pin "P1_9") (pinfunction "GND_P1_9") (pintype "power_in"))
      (node (ref "U$2") (pin "P6_2") (pinfunction "GND_P6_2") (pintype "power_in"))
      (node (ref "U$3") (pin "P$13") (pinfunction "GND_P$13") (pintype "bidirectional"))
      (node (ref "U$3") (pin "P$4") (pinfunction "GND_P$4") (pintype "bidirectional"))
      (node (ref "U$4") (pin "P$13") (pinfunction "GND_P$13") (pintype "bidirectional"))
      (node (ref "U$4") (pin "P$4") (pinfunction "GND_P$4") (pintype "bidirectional"))
      (node (ref "U$5") (pin "P$13") (pinfunction "GND_P$13") (pintype "bidirectional"))
      (node (ref "U$5") (pin "P$4") (pinfunction "GND_P$4") (pintype "bidirectional"))
      (node (ref "U$6") (pin "P$13") (pinfunction "GND_P$13") (pintype "bidirectional"))
      (node (ref "U$6") (pin "P$4") (pinfunction "GND_P$4") (pintype "bidirectional"))
      (node (ref "U$7") (pin "P$13") (pinfunction "GND_P$13") (pintype "bidirectional"))
      (node (ref "U$7") (pin "P$4") (pinfunction "GND_P$4") (pintype "bidirectional"))
      (node (ref "U$8") (pin "P$13") (pinfunction "GND_P$13") (pintype "bidirectional"))
      (node (ref "U$8") (pin "P$4") (pinfunction "GND_P$4") (pintype "bidirectional"))
      (node (ref "X10") (pin "3") (pinfunction "S_3") (pintype "passive"))
      (node (ref "X11") (pin "3") (pinfunction "S_3") (pintype "passive"))
      (node (ref "X12") (pin "3") (pinfunction "S_3") (pintype "passive"))
      (node (ref "X13") (pin "3") (pinfunction "S_3") (pintype "passive"))
      (node (ref "X14") (pin "3") (pinfunction "S_3") (pintype "passive"))
      (node (ref "X4") (pin "3") (pinfunction "S_3") (pintype "passive"))
      (node (ref "X5") (pin "3") (pinfunction "S_3") (pintype "passive"))
      (node (ref "X6") (pin "3") (pinfunction "S_3") (pintype "passive"))
      (node (ref "X7") (pin "3") (pinfunction "S_3") (pintype "passive"))
      (node (ref "X8") (pin "4") (pinfunction "S_4") (pintype "passive"))
      (node (ref "X9") (pin "3") (pinfunction "S_3") (pintype "passive"))
    )
    (net (code "14") (name "I2C-SCL") (class "Default")
      (node (ref "U$1") (pin "19/A5") (pinfunction "19/A5_19/A5") (pintype "bidirectional"))
      (node (ref "U$2") (pin "P1_5") (pinfunction "GPIO3/I2C1_SCL_P1_5") (pintype "bidirectional"))
      (node (ref "X12") (pin "1") (pinfunction "S_1") (pintype "passive"))
    )
    (net (code "15") (name "I2C-SDA") (class "Default")
      (node (ref "U$1") (pin "18/A4") (pinfunction "18/A4_18/A4") (pintype "bidirectional"))
      (node (ref "U$2") (pin "P1_3") (pinfunction "GPIO2/I2C1_SDA_P1_3") (pintype "bidirectional"))
      (node (ref "X12") (pin "2") (pinfunction "S_2") (pintype "passive"))
    )
    (net (code "16") (name "MOTOR-D-1") (class "Default")
      (node (ref "U$4") (pin "P$7") (pinfunction "OUTA_P$7") (pintype "bidirectional"))
      (node (ref "X2") (pin "1") (pinfunction "S_1") (pintype "passive"))
    )
    (net (code "17") (name "MOTOR-D-2") (class "Default")
      (node (ref "U$4") (pin "P$10") (pinfunction "OUTB_P$10") (pintype "bidirectional"))
      (node (ref "X2") (pin "2") (pinfunction "S_2") (pintype "passive"))
    )
    (net (code "18") (name "MOTOR-D-BRAKE") (class "Default")
      (node (ref "J2") (pin "3") (pinfunction "S_3") (pintype "passive"))
      (node (ref "U$1") (pin "8") (pinfunction "8_8") (pintype "bidirectional"))
      (node (ref "U$4") (pin "P$2") (pinfunction "MODE_P$2") (pintype "bidirectional"))
    )
    (net (code "19") (name "MOTOR-D-DIR") (class "Default")
      (node (ref "J2") (pin "4") (pinfunction "S_4") (pintype "passive"))
      (node (ref "U$1") (pin "7") (pinfunction "7_7") (pintype "bidirectional"))
      (node (ref "U$4") (pin "P$3") (pinfunction "PHASE_P$3") (pintype "bidirectional"))
    )
    (net (code "20") (name "MOTOR-D-PWM") (class "Default")
      (node (ref "J2") (pin "5") (pinfunction "S_5") (pintype "passive"))
      (node (ref "U$1") (pin "9") (pinfunction "9_9") (pintype "bidirectional"))
      (node (ref "U$4") (pin "P$6") (pinfunction "ENABLE_P$6") (pintype "bidirectional"))
    )
    (net (code "21") (name "MOTOR-D-SENSE") (class "Default")
      (node (ref "J2") (pin "2") (pinfunction "S_2") (pintype "passive"))
      (node (ref "U$1") (pin "23/A9") (pinfunction "23/A9_23/A9") (pintype "bidirectional"))
      (node (ref "U$4") (pin "P$8") (pinfunction "SENSE_P$8") (pintype "bidirectional"))
    )
    (net (code "22") (name "MOTOR-G-1") (class "Default")
      (node (ref "U$3") (pin "P$7") (pinfunction "OUTA_P$7") (pintype "bidirectional"))
      (node (ref "X1") (pin "1") (pinfunction "S_1") (pintype "passive"))
    )
    (net (code "23") (name "MOTOR-G-2") (class "Default")
      (node (ref "U$3") (pin "P$10") (pinfunction "OUTB_P$10") (pintype "bidirectional"))
      (node (ref "X1") (pin "2") (pinfunction "S_2") (pintype "passive"))
    )
    (net (code "24") (name "MOTOR-G-BRAKE") (class "Default")
      (node (ref "J1") (pin "3") (pinfunction "S_3") (pintype "passive"))
      (node (ref "U$1") (pin "12") (pinfunction "12_12") (pintype "bidirectional"))
      (node (ref "U$3") (pin "P$2") (pinfunction "MODE_P$2") (pintype "bidirectional"))
    )
    (net (code "25") (name "MOTOR-G-DIR") (class "Default")
      (node (ref "J1") (pin "4") (pinfunction "S_4") (pintype "passive"))
      (node (ref "U$1") (pin "11") (pinfunction "11_11") (pintype "bidirectional"))
      (node (ref "U$3") (pin "P$3") (pinfunction "PHASE_P$3") (pintype "bidirectional"))
    )
    (net (code "26") (name "MOTOR-G-PWM") (class "Default")
      (node (ref "J1") (pin "5") (pinfunction "S_5") (pintype "passive"))
      (node (ref "U$1") (pin "10") (pinfunction "10_10") (pintype "bidirectional"))
      (node (ref "U$3") (pin "P$6") (pinfunction "ENABLE_P$6") (pintype "bidirectional"))
    )
    (net (code "27") (name "MOTOR-G-SENSE") (class "Default")
      (node (ref "J1") (pin "2") (pinfunction "S_2") (pintype "passive"))
      (node (ref "U$1") (pin "22/A8") (pinfunction "22/A8_22/A8") (pintype "bidirectional"))
      (node (ref "U$3") (pin "P$8") (pinfunction "SENSE_P$8") (pintype "bidirectional"))
    )
    (net (code "28") (name "N$15") (class "Default")
      (node (ref "U$2") (pin "P1_24") (pinfunction "GPIO8/SPI0_CE0_P1_24") (pintype "bidirectional"))
    )
    (net (code "29") (name "N$19") (class "Default")
      (node (ref "U$2") (pin "P1_23") (pinfunction "GPIO11/SPI0_SLCK_P1_23") (pintype "bidirectional"))
    )
    (net (code "30") (name "Net-(J4A-S)") (class "Default")
      (node (ref "H3") (pin "1") (pinfunction "1_1") (pintype "passive"))
      (node (ref "H4") (pin "1") (pinfunction "1_1") (pintype "passive"))
      (node (ref "J4") (pin "1") (pinfunction "S_1") (pintype "passive"))
    )
    (net (code "31") (name "Net-(J4B-S)") (class "Default")
      (node (ref "H1") (pin "1") (pinfunction "1_1") (pintype "passive"))
      (node (ref "H2") (pin "1") (pinfunction "1_1") (pintype "passive"))
      (node (ref "J4") (pin "2") (pinfunction "S_2") (pintype "passive"))
    )
    (net (code "32") (name "Net-(J6A-S)") (class "Default")
      (node (ref "H7") (pin "1") (pinfunction "1_1") (pintype "passive"))
      (node (ref "H8") (pin "1") (pinfunction "1_1") (pintype "passive"))
      (node (ref "J6") (pin "1") (pinfunction "S_1") (pintype "passive"))
    )
    (net (code "33") (name "Net-(J6B-S)") (class "Default")
      (node (ref "H5") (pin "1") (pinfunction "1_1") (pintype "passive"))
      (node (ref "H6") (pin "1") (pinfunction "1_1") (pintype "passive"))
      (node (ref "J6") (pin "2") (pinfunction "S_2") (pintype "passive"))
    )
    (net (code "34") (name "Net-(J8A-S)") (class "Default")
      (node (ref "J8") (pin "1") (pinfunction "S_1") (pintype "passive"))
      (node (ref "PAD1") (pin "1") (pinfunction "P_1") (pintype "passive"))
      (node (ref "PAD3") (pin "1") (pinfunction "P_1") (pintype "passive"))
    )
    (net (code "35") (name "Net-(J8B-S)") (class "Default")
      (node (ref "J8") (pin "2") (pinfunction "S_2") (pintype "passive"))
      (node (ref "PAD2") (pin "1") (pinfunction "P_1") (pintype "passive"))
      (node (ref "PAD4") (pin "1") (pinfunction "P_1") (pintype "passive"))
    )
    (net (code "36") (name "Net-(LED1-C)") (class "Default")
      (node (ref "LED1") (pin "K") (pinfunction "C_K") (pintype "passive"))
      (node (ref "R21") (pin "1") (pinfunction "1_1") (pintype "passive"))
    )
    (net (code "37") (name "Net-(LED2-C)") (class "Default")
      (node (ref "LED2") (pin "K") (pinfunction "C_K") (pintype "passive"))
      (node (ref "R26") (pin "1") (pinfunction "1_1") (pintype "passive"))
    )
    (net (code "38") (name "Net-(U$5-CP1)") (class "Default")
      (node (ref "C12") (pin "2") (pinfunction "2_2") (pintype "passive"))
      (node (ref "U$5") (pin "P$11") (pinfunction "CP1_P$11") (pintype "bidirectional"))
      (node (ref "U$6") (pin "P$11") (pinfunction "CP1_P$11") (pintype "bidirectional"))
    )
    (net (code "39") (name "Net-(U$5-CP2)") (class "Default")
      (node (ref "C12") (pin "1") (pinfunction "1_1") (pintype "passive"))
      (node (ref "U$5") (pin "P$12") (pinfunction "CP2_P$12") (pintype "bidirectional"))
      (node (ref "U$6") (pin "P$12") (pinfunction "CP2_P$12") (pintype "bidirectional"))
    )
    (net (code "40") (name "Net-(U$5-ENABLE)") (class "Default")
      (node (ref "U$5") (pin "P$6") (pinfunction "ENABLE_P$6") (pintype "bidirectional"))
      (node (ref "U$6") (pin "P$6") (pinfunction "ENABLE_P$6") (pintype "bidirectional"))
    )
    (net (code "41") (name "Net-(U$5-MODE)") (class "Default")
      (node (ref "U$5") (pin "P$2") (pinfunction "MODE_P$2") (pintype "bidirectional"))
      (node (ref "U$6") (pin "P$2") (pinfunction "MODE_P$2") (pintype "bidirectional"))
    )
    (net (code "42") (name "Net-(U$5-NFAULT)") (class "Default")
      (node (ref "R21") (pin "2") (pinfunction "2_2") (pintype "passive"))
      (node (ref "U$5") (pin "P$1") (pinfunction "NFAULT_P$1") (pintype "bidirectional"))
    )
    (net (code "43") (name "Net-(U$5-OUTA)") (class "Default")
      (node (ref "U$5") (pin "P$7") (pinfunction "OUTA_P$7") (pintype "bidirectional"))
      (node (ref "U$6") (pin "P$7") (pinfunction "OUTA_P$7") (pintype "bidirectional"))
    )
    (net (code "44") (name "Net-(U$5-OUTB)") (class "Default")
      (node (ref "U$5") (pin "P$10") (pinfunction "OUTB_P$10") (pintype "bidirectional"))
      (node (ref "U$6") (pin "P$10") (pinfunction "OUTB_P$10") (pintype "bidirectional"))
    )
    (net (code "45") (name "Net-(U$5-PHASE)") (class "Default")
      (node (ref "U$5") (pin "P$3") (pinfunction "PHASE_P$3") (pintype "bidirectional"))
      (node (ref "U$6") (pin "P$3") (pinfunction "PHASE_P$3") (pintype "bidirectional"))
    )
    (net (code "46") (name "Net-(U$5-SENSE)") (class "Default")
      (node (ref "R20") (pin "2") (pinfunction "2_2") (pintype "passive"))
      (node (ref "U$5") (pin "P$8") (pinfunction "SENSE_P$8") (pintype "bidirectional"))
      (node (ref "U$6") (pin "P$8") (pinfunction "SENSE_P$8") (pintype "bidirectional"))
    )
    (net (code "47") (name "Net-(U$5-SLEEP)") (class "Default")
      (node (ref "R19") (pin "2") (pinfunction "2_2") (pintype "passive"))
      (node (ref "U$5") (pin "P$5") (pinfunction "SLEEP_P$5") (pintype "bidirectional"))
    )
    (net (code "48") (name "Net-(U$5-VBB)") (class "Default")
      (node (ref "C14") (pin "1") (pinfunction "1_1") (pintype "passive"))
      (node (ref "C15") (pin "2") (pinfunction "2_2") (pintype "passive"))
      (node (ref "U$5") (pin "P$9") (pinfunction "VBB_P$9") (pintype "bidirectional"))
      (node (ref "U$6") (pin "P$9") (pinfunction "VBB_P$9") (pintype "bidirectional"))
    )
    (net (code "49") (name "Net-(U$5-VCP)") (class "Default")
      (node (ref "C15") (pin "1") (pinfunction "1_1") (pintype "passive"))
      (node (ref "U$5") (pin "P$14") (pinfunction "VCP_P$14") (pintype "bidirectional"))
      (node (ref "U$6") (pin "P$14") (pinfunction "VCP_P$14") (pintype "bidirectional"))
    )
    (net (code "50") (name "Net-(U$5-VREG)") (class "Default")
      (node (ref "C13") (pin "1") (pinfunction "1_1") (pintype "passive"))
      (node (ref "U$5") (pin "P$15") (pinfunction "VREG_P$15") (pintype "bidirectional"))
      (node (ref "U$6") (pin "P$15") (pinfunction "VREG_P$15") (pintype "bidirectional"))
    )
    (net (code "51") (name "Net-(U$6-NFAULT)") (class "Default")
      (node (ref "LED1") (pin "A") (pinfunction "A_A") (pintype "passive"))
      (node (ref "U$6") (pin "P$1") (pinfunction "NFAULT_P$1") (pintype "bidirectional"))
    )
    (net (code "52") (name "Net-(U$6-SLEEP)") (class "Default")
      (node (ref "R19") (pin "1") (pinfunction "1_1") (pintype "passive"))
      (node (ref "U$6") (pin "P$5") (pinfunction "SLEEP_P$5") (pintype "bidirectional"))
    )
    (net (code "53") (name "Net-(U$7-CP1)") (class "Default")
      (node (ref "C20") (pin "2") (pinfunction "2_2") (pintype "passive"))
      (node (ref "U$7") (pin "P$11") (pinfunction "CP1_P$11") (pintype "bidirectional"))
      (node (ref "U$8") (pin "P$11") (pinfunction "CP1_P$11") (pintype "bidirectional"))
    )
    (net (code "54") (name "Net-(U$7-CP2)") (class "Default")
      (node (ref "C20") (pin "1") (pinfunction "1_1") (pintype "passive"))
      (node (ref "U$7") (pin "P$12") (pinfunction "CP2_P$12") (pintype "bidirectional"))
      (node (ref "U$8") (pin "P$12") (pinfunction "CP2_P$12") (pintype "bidirectional"))
    )
    (net (code "55") (name "Net-(U$7-ENABLE)") (class "Default")
      (node (ref "U$7") (pin "P$6") (pinfunction "ENABLE_P$6") (pintype "bidirectional"))
      (node (ref "U$8") (pin "P$6") (pinfunction "ENABLE_P$6") (pintype "bidirectional"))
    )
    (net (code "56") (name "Net-(U$7-MODE)") (class "Default")
      (node (ref "U$7") (pin "P$2") (pinfunction "MODE_P$2") (pintype "bidirectional"))
      (node (ref "U$8") (pin "P$2") (pinfunction "MODE_P$2") (pintype "bidirectional"))
    )
    (net (code "57") (name "Net-(U$7-NFAULT)") (class "Default")
      (node (ref "R26") (pin "2") (pinfunction "2_2") (pintype "passive"))
      (node (ref "U$7") (pin "P$1") (pinfunction "NFAULT_P$1") (pintype "bidirectional"))
    )
    (net (code "58") (name "Net-(U$7-OUTA)") (class "Default")
      (node (ref "U$7") (pin "P$7") (pinfunction "OUTA_P$7") (pintype "bidirectional"))
      (node (ref "U$8") (pin "P$7") (pinfunction "OUTA_P$7") (pintype "bidirectional"))
    )
    (net (code "59") (name "Net-(U$7-OUTB)") (class "Default")
      (node (ref "U$7") (pin "P$10") (pinfunction "OUTB_P$10") (pintype "bidirectional"))
      (node (ref "U$8") (pin "P$10") (pinfunction "OUTB_P$10") (pintype "bidirectional"))
    )
    (net (code "60") (name "Net-(U$7-PHASE)") (class "Default")
      (node (ref "U$7") (pin "P$3") (pinfunction "PHASE_P$3") (pintype "bidirectional"))
      (node (ref "U$8") (pin "P$3") (pinfunction "PHASE_P$3") (pintype "bidirectional"))
    )
    (net (code "61") (name "Net-(U$7-SENSE)") (class "Default")
      (node (ref "R25") (pin "2") (pinfunction "2_2") (pintype "passive"))
      (node (ref "U$7") (pin "P$8") (pinfunction "SENSE_P$8") (pintype "bidirectional"))
      (node (ref "U$8") (pin "P$8") (pinfunction "SENSE_P$8") (pintype "bidirectional"))
    )
    (net (code "62") (name "Net-(U$7-SLEEP)") (class "Default")
      (node (ref "R24") (pin "2") (pinfunction "2_2") (pintype "passive"))
      (node (ref "U$7") (pin "P$5") (pinfunction "SLEEP_P$5") (pintype "bidirectional"))
    )
    (net (code "63") (name "Net-(U$7-VBB)") (class "Default")
      (node (ref "C22") (pin "1") (pinfunction "1_1") (pintype "passive"))
      (node (ref "C23") (pin "2") (pinfunction "2_2") (pintype "passive"))
      (node (ref "U$7") (pin "P$9") (pinfunction "VBB_P$9") (pintype "bidirectional"))
      (node (ref "U$8") (pin "P$9") (pinfunction "VBB_P$9") (pintype "bidirectional"))
    )
    (net (code "64") (name "Net-(U$7-VCP)") (class "Default")
      (node (ref "C23") (pin "1") (pinfunction "1_1") (pintype "passive"))
      (node (ref "U$7") (pin "P$14") (pinfunction "VCP_P$14") (pintype "bidirectional"))
      (node (ref "U$8") (pin "P$14") (pinfunction "VCP_P$14") (pintype "bidirectional"))
    )
    (net (code "65") (name "Net-(U$7-VREG)") (class "Default")
      (node (ref "C21") (pin "1") (pinfunction "1_1") (pintype "passive"))
      (node (ref "U$7") (pin "P$15") (pinfunction "VREG_P$15") (pintype "bidirectional"))
      (node (ref "U$8") (pin "P$15") (pinfunction "VREG_P$15") (pintype "bidirectional"))
    )
    (net (code "66") (name "Net-(U$8-NFAULT)") (class "Default")
      (node (ref "LED2") (pin "A") (pinfunction "A_A") (pintype "passive"))
      (node (ref "U$8") (pin "P$1") (pinfunction "NFAULT_P$1") (pintype "bidirectional"))
    )
    (net (code "67") (name "Net-(U$8-SLEEP)") (class "Default")
      (node (ref "R24") (pin "1") (pinfunction "1_1") (pintype "passive"))
      (node (ref "U$8") (pin "P$5") (pinfunction "SLEEP_P$5") (pintype "bidirectional"))
    )
    (net (code "68") (name "Net-(X3A-S)") (class "Default")
      (node (ref "U$1") (pin "VIN") (pinfunction "VIN_VIN") (pintype "power_in"))
      (node (ref "X3") (pin "1") (pinfunction "S_1") (pintype "passive"))
    )
    (net (code "69") (name "RESET") (class "Default")
      (node (ref "U$2") (pin "P6_1") (pinfunction "RESET_P6_1") (pintype "power_in"))
    )
    (net (code "70") (name "RXTEENSY") (class "Default")
      (node (ref "U$1") (pin "0") (pinfunction "0_0") (pintype "bidirectional"))
      (node (ref "U$2") (pin "P1_8") (pinfunction "UART0_TXD/GPIO14_P1_8") (pintype "bidirectional"))
    )
    (net (code "71") (name "SRV1") (class "Default")
      (node (ref "Q1") (pin "3") (pinfunction "D_3") (pintype "passive"))
      (node (ref "R2") (pin "1") (pinfunction "1_1") (pintype "passive"))
      (node (ref "X11") (pin "1") (pinfunction "S_1") (pintype "passive"))
    )
    (net (code "72") (name "SRV2") (class "Default")
      (node (ref "Q2") (pin "3") (pinfunction "D_3") (pintype "passive"))
      (node (ref "R4") (pin "1") (pinfunction "1_1") (pintype "passive"))
      (node (ref "X4") (pin "1") (pinfunction "S_1") (pintype "passive"))
    )
    (net (code "73") (name "SRV3") (class "Default")
      (node (ref "Q3") (pin "3") (pinfunction "D_3") (pintype "passive"))
      (node (ref "R10") (pin "1") (pinfunction "1_1") (pintype "passive"))
      (node (ref "X6") (pin "1") (pinfunction "S_1") (pintype "passive"))
    )
    (net (code "74") (name "SRV4") (class "Default")
      (node (ref "Q4") (pin "3") (pinfunction "D_3") (pintype "passive"))
      (node (ref "R12") (pin "1") (pinfunction "1_1") (pintype "passive"))
      (node (ref "X7") (pin "1") (pinfunction "S_1") (pintype "passive"))
    )
    (net (code "75") (name "SRV5") (class "Default")
      (node (ref "Q5") (pin "3") (pinfunction "D_3") (pintype "passive"))
      (node (ref "R16") (pin "1") (pinfunction "1_1") (pintype "passive"))
      (node (ref "X5") (pin "1") (pinfunction "S_1") (pintype "passive"))
    )
    (net (code "76") (name "SRV6") (class "Default")
      (node (ref "Q6") (pin "3") (pinfunction "D_3") (pintype "passive"))
      (node (ref "R18") (pin "1") (pinfunction "1_1") (pintype "passive"))
      (node (ref "X9") (pin "1") (pinfunction "S_1") (pintype "passive"))
    )
    (net (code "77") (name "SRV8") (class "Default")
      (node (ref "Q7") (pin "3") (pinfunction "D_3") (pintype "passive"))
      (node (ref "R6") (pin "1") (pinfunction "1_1") (pintype "passive"))
      (node (ref "X10") (pin "1") (pinfunction "S_1") (pintype "passive"))
    )
    (net (code "78") (name "SRV9") (class "Default")
      (node (ref "Q8") (pin "3") (pinfunction "D_3") (pintype "passive"))
      (node (ref "R8") (pin "1") (pinfunction "1_1") (pintype "passive"))
      (node (ref "X13") (pin "1") (pinfunction "S_1") (pintype "passive"))
    )
    (net (code "79") (name "SRV10") (class "Default")
      (node (ref "Q9") (pin "3") (pinfunction "D_3") (pintype "passive"))
      (node (ref "R14") (pin "1") (pinfunction "1_1") (pintype "passive"))
      (node (ref "X14") (pin "1") (pinfunction "S_1") (pintype "passive"))
    )
    (net (code "80") (name "SRV13.3") (class "Default")
      (node (ref "Q1") (pin "2") (pinfunction "S_2") (pintype "passive"))
      (node (ref "R1") (pin "1") (pinfunction "1_1") (pintype "passive"))
      (node (ref "U$1") (pin "14/A0") (pinfunction "14/A0_14/A0") (pintype "bidirectional"))
    )
    (net (code "81") (name "SRV23.3") (class "Default")
      (node (ref "Q2") (pin "2") (pinfunction "S_2") (pintype "passive"))
      (node (ref "R3") (pin "1") (pinfunction "1_1") (pintype "passive"))
      (node (ref "U$1") (pin "15/A1") (pinfunction "15/A1_15/A1") (pintype "bidirectional"))
    )
    (net (code "82") (name "SRV33.3") (class "Default")
      (node (ref "Q3") (pin "2") (pinfunction "S_2") (pintype "passive"))
      (node (ref "R9") (pin "1") (pinfunction "1_1") (pintype "passive"))
      (node (ref "U$1") (pin "16/A2") (pinfunction "16/A2_16/A2") (pintype "bidirectional"))
    )
    (net (code "83") (name "SRV43.3") (class "Default")
      (node (ref "Q4") (pin "2") (pinfunction "S_2") (pintype "passive"))
      (node (ref "R11") (pin "1") (pinfunction "1_1") (pintype "passive"))
      (node (ref "U$1") (pin "17/A3") (pinfunction "17/A3_17/A3") (pintype "bidirectional"))
    )
    (net (code "84") (name "SRV53.3") (class "Default")
      (node (ref "Q5") (pin "2") (pinfunction "S_2") (pintype "passive"))
      (node (ref "R15") (pin "1") (pinfunction "1_1") (pintype "passive"))
      (node (ref "U$1") (pin "20/A6") (pinfunction "20/A6_20/A6") (pintype "bidirectional"))
    )
    (net (code "85") (name "SRV63.3") (class "Default")
      (node (ref "Q6") (pin "2") (pinfunction "S_2") (pintype "passive"))
      (node (ref "R17") (pin "1") (pinfunction "1_1") (pintype "passive"))
      (node (ref "U$1") (pin "21/A7") (pinfunction "21/A7_21/A7") (pintype "bidirectional"))
    )
    (net (code "86") (name "SRV83.3") (class "Default")
      (node (ref "Q7") (pin "2") (pinfunction "S_2") (pintype "passive"))
      (node (ref "R5") (pin "1") (pinfunction "1_1") (pintype "passive"))
      (node (ref "U$2") (pin "P1_19") (pinfunction "GPIO10/SPI0_MOSI_P1_19") (pintype "bidirectional"))
    )
    (net (code "87") (name "SRV93.3") (class "Default")
      (node (ref "Q8") (pin "2") (pinfunction "S_2") (pintype "passive"))
      (node (ref "R7") (pin "1") (pinfunction "1_1") (pintype "passive"))
      (node (ref "U$2") (pin "P1_21") (pinfunction "GPIO9/SPI0_MISO_P1_21") (pintype "bidirectional"))
    )
    (net (code "88") (name "SRV103.3") (class "Default")
      (node (ref "Q9") (pin "2") (pinfunction "S_2") (pintype "passive"))
      (node (ref "R13") (pin "1") (pinfunction "1_1") (pintype "passive"))
      (node (ref "U$2") (pin "P1_26") (pinfunction "GPIO7/SPI0_CE1_P1_26") (pintype "bidirectional"))
    )
    (net (code "89") (name "TXTEENSY") (class "Default")
      (node (ref "U$1") (pin "1") (pinfunction "1_1") (pintype "bidirectional"))
      (node (ref "U$2") (pin "P1_10") (pinfunction "UART0_RXD/GPIO15_P1_10") (pintype "bidirectional"))
    )
    (net (code "90") (name "VBAT") (class "Default")
      (node (ref "U$1") (pin "VBAT") (pinfunction "VBAT_VBAT") (pintype "power_in"))
    )
    (net (code "91") (name "unconnected-(U$1-Pad2)") (class "Default")
      (node (ref "U$1") (pin "2") (pinfunction "2_2") (pintype "bidirectional"))
    )
    (net (code "92") (name "unconnected-(U$1-Pad13)") (class "Default")
      (node (ref "U$1") (pin "13") (pinfunction "13_13") (pintype "bidirectional"))
    )
    (net (code "93") (name "unconnected-(U$1-PadPGM)") (class "Default")
      (node (ref "U$1") (pin "PGM") (pinfunction "PGM_PGM") (pintype "bidirectional"))
    )
    (net (code "94") (name "unconnected-(U$1-PadRESET)") (class "Default")
      (node (ref "U$1") (pin "RESET") (pinfunction "RESET_RESET") (pintype "bidirectional"))
    )
    (net (code "95") (name "unconnected-(U$2-GPIO4{slash}GPCLK0-PadP1_7)") (class "Default")
      (node (ref "U$2") (pin "P1_7") (pinfunction "GPIO4/GPCLK0_P1_7") (pintype "bidirectional"))
    )
    (net (code "96") (name "unconnected-(U$2-GPIO22-PadP1_15)") (class "Default")
      (node (ref "U$2") (pin "P1_15") (pinfunction "GPIO22_P1_15") (pintype "bidirectional"))
    )
    (net (code "97") (name "unconnected-(U$2-GPIO23-PadP1_16)") (class "Default")
      (node (ref "U$2") (pin "P1_16") (pinfunction "GPIO23_P1_16") (pintype "bidirectional"))
    )
    (net (code "98") (name "unconnected-(U$2-GPIO24-PadP1_18)") (class "Default")
      (node (ref "U$2") (pin "P1_18") (pinfunction "GPIO24_P1_18") (pintype "bidirectional"))
    )
    (net (code "99") (name "unconnected-(U$2-GPIO25-PadP1_22)") (class "Default")
      (node (ref "U$2") (pin "P1_22") (pinfunction "GPIO25_P1_22") (pintype "bidirectional"))
    )
    (net (code "100") (name "unconnected-(U$2-GPIO27-PadP1_13)") (class "Default")
      (node (ref "U$2") (pin "P1_13") (pinfunction "GPIO27_P1_13") (pintype "bidirectional"))
    )
    (net (code "101") (name "unconnected-(U$2-PWM0{slash}GPIO18-PadP1_12)") (class "Default")
      (node (ref "U$2") (pin "P1_12") (pinfunction "PWM0/GPIO18_P1_12") (pintype "bidirectional"))
    )
    (net (code "102") (name "unconnected-(U$2-UART0_RTS{slash}GPIO17-PadP1_11)") (class "Default")
      (node (ref "U$2") (pin "P1_11") (pinfunction "UART0_RTS/GPIO17_P1_11") (pintype "bidirectional"))
    )
    (net (code "103") (name "unconnected-(U$3-CP1-PadP$11)") (class "Default")
      (node (ref "U$3") (pin "P$11") (pinfunction "CP1_P$11") (pintype "bidirectional"))
    )
    (net (code "104") (name "unconnected-(U$3-CP2-PadP$12)") (class "Default")
      (node (ref "U$3") (pin "P$12") (pinfunction "CP2_P$12") (pintype "bidirectional"))
    )
    (net (code "105") (name "unconnected-(U$3-VCP-PadP$14)") (class "Default")
      (node (ref "U$3") (pin "P$14") (pinfunction "VCP_P$14") (pintype "bidirectional"))
    )
    (net (code "106") (name "unconnected-(U$3-VREG-PadP$15)") (class "Default")
      (node (ref "U$3") (pin "P$15") (pinfunction "VREG_P$15") (pintype "bidirectional"))
    )
    (net (code "107") (name "unconnected-(U$4-CP1-PadP$11)") (class "Default")
      (node (ref "U$4") (pin "P$11") (pinfunction "CP1_P$11") (pintype "bidirectional"))
    )
    (net (code "108") (name "unconnected-(U$4-CP2-PadP$12)") (class "Default")
      (node (ref "U$4") (pin "P$12") (pinfunction "CP2_P$12") (pintype "bidirectional"))
    )
    (net (code "109") (name "unconnected-(U$4-VCP-PadP$14)") (class "Default")
      (node (ref "U$4") (pin "P$14") (pinfunction "VCP_P$14") (pintype "bidirectional"))
    )
    (net (code "110") (name "unconnected-(U$4-VREG-PadP$15)") (class "Default")
      (node (ref "U$4") (pin "P$15") (pinfunction "VREG_P$15") (pintype "bidirectional"))
    )
  )
)
